# Atmega328p.net
KiCad netlist of a schematic drawn in Altium Designer
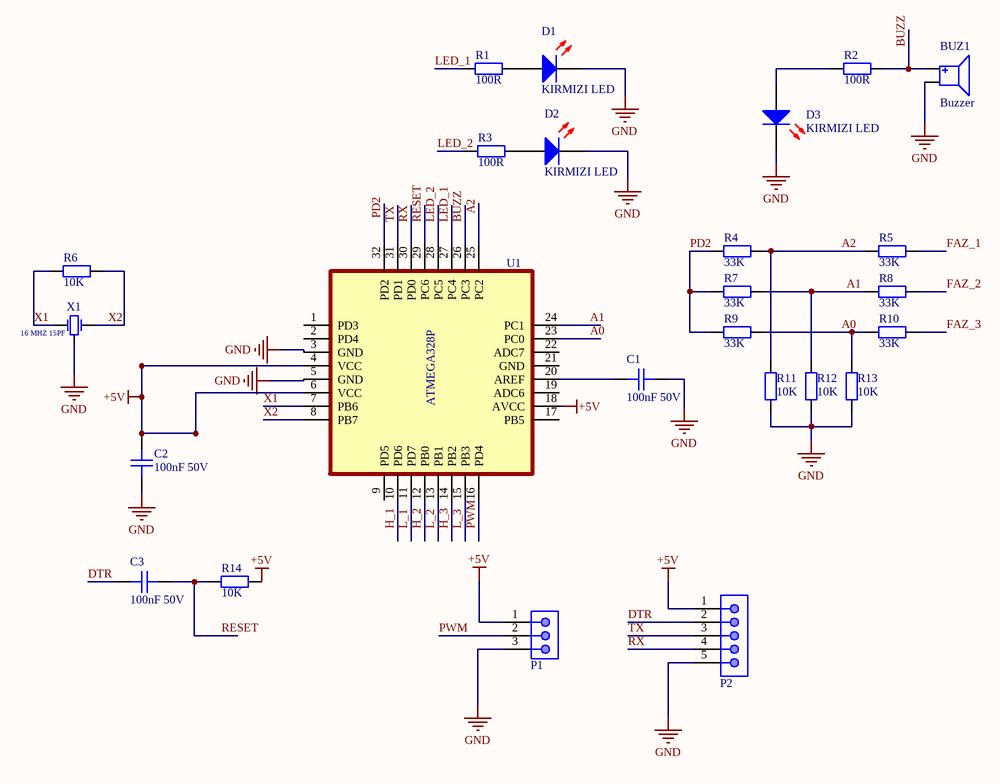
[diagram p0: Atmega328p.SchDoc]

(export (version "E")
  (design (tool "Eeschema 10.0.6"))
  (components
    (comp (ref "BUZ1")
      (value "BUZZER MAGN 3.6V 7.5X7.5MM SMD")
      (footprint "BUZ: CMT-7525")
      (fields (field (name "DEGER") "Buzzer"))
      (libsource (lib "PROJE") (part "Buzzer(CMT-7525-80-SMT-TR)"))
    )
    (comp (ref "C1")
      (value "CAP CER 0.1UF 50V X7R 0805")
      (footprint "CAP 0805/2012")
      (description "0.1µF ±10% 50V Ceramic Capacitor X7R 0805 (2012 Metric)")
      (fields (field (name "DEGER") "100nF 50V"))
      (libsource (lib "PROJE") (part "100nF 50V 0805"))
    )
    (comp (ref "C2")
      (value "CAP CER 0.1UF 50V X7R 0805")
      (footprint "CAP 0805/2012")
      (description "0.1µF ±10% 50V Ceramic Capacitor X7R 0805 (2012 Metric)")
      (fields (field (name "DEGER") "100nF 50V"))
      (libsource (lib "PROJE") (part "100nF 50V 0805"))
    )
    (comp (ref "C3")
      (value "CAP CER 0.1UF 50V X7R 0805")
      (footprint "CAP 0805/2012")
      (description "0.1µF ±10% 50V Ceramic Capacitor X7R 0805 (2012 Metric)")
      (fields (field (name "DEGER") "100nF 50V"))
      (libsource (lib "PROJE") (part "100nF 50V 0805"))
    )
    (comp (ref "D1")
      (value "Red 645nm LED Indication - Discrete 1.8V 0805")
      (footprint "SMD: LED 0805/2012 RED")
      (description "LED RED DIFFUSED 0805 SMD")
      (fields (field (name "DEGER") "KIRMIZI LED"))
      (libsource (lib "PROJE") (part "LED_Kırmızı"))
    )
    (comp (ref "D2")
      (value "Red 645nm LED Indication - Discrete 1.8V 0805")
      (footprint "SMD: LED 0805/2012 RED")
      (description "LED RED DIFFUSED 0805 SMD")
      (fields (field (name "DEGER") "KIRMIZI LED"))
      (libsource (lib "PROJE") (part "LED_Kırmızı"))
    )
    (comp (ref "D3")
      (value "Red 645nm LED Indication - Discrete 1.8V 0805")
      (footprint "SMD: LED 0805/2012 RED")
      (description "LED RED DIFFUSED 0805 SMD")
      (fields (field (name "DEGER") "KIRMIZI LED"))
      (libsource (lib "PROJE") (part "LED_Kırmızı"))
    )
    (comp (ref "P1")
      (value "WR-PHD 2.54 mm Angled Socket Header")
      (footprint "PWM_CONN")
      (libsource (lib "PROJE") (part "HDR(1X3)"))
    )
    (comp (ref "P2")
      (value "WR-PHD 2.54 mm Angled Socket Header")
      (footprint "TTL_CONN_5")
      (libsource (lib "PROJE") (part "HDR(1X5)"))
    )
    (comp (ref "R1")
      (value "RES SMD 100 OHM 1% 1/8W 0805")
      (footprint "RES_0805")
      (description "100 Ohms ±1% 0.125W, 1/8W Chip Resistor 0805 (2012 Metric) Moisture Resistant Thick Film")
      (fields (field (name "DEGER") "100R"))
      (libsource (lib "PROJE") (part "100R 0805"))
    )
    (comp (ref "R2")
      (value "RES SMD 100 OHM 1% 1/8W 0805")
      (footprint "RES_0805")
      (description "100 Ohms ±1% 0.125W, 1/8W Chip Resistor 0805 (2012 Metric) Moisture Resistant Thick Film")
      (fields (field (name "DEGER") "100R"))
      (libsource (lib "PROJE") (part "100R 0805"))
    )
    (comp (ref "R3")
      (value "RES SMD 100 OHM 1% 1/8W 0805")
      (footprint "RES_0805")
      (description "100 Ohms ±1% 0.125W, 1/8W Chip Resistor 0805 (2012 Metric) Moisture Resistant Thick Film")
      (fields (field (name "DEGER") "100R"))
      (libsource (lib "PROJE") (part "100R 0805"))
    )
    (comp (ref "R4")
      (value "RES SMD 33K OHM 1% 1/8W 0805")
      (footprint "RES_0805")
      (description "33 kOhms ±1% 0.125W, 1/8W Chip Resistor 0805 (2012 Metric) Moisture Resistant Thick Film")
      (fields (field (name "DEGER") "33K"))
      (libsource (lib "PROJE") (part "33K 0805"))
    )
    (comp (ref "R5")
      (value "RES SMD 33K OHM 1% 1/8W 0805")
      (footprint "RES_0805")
      (description "33 kOhms ±1% 0.125W, 1/8W Chip Resistor 0805 (2012 Metric) Moisture Resistant Thick Film")
      (fields (field (name "DEGER") "33K"))
      (libsource (lib "PROJE") (part "33K 0805"))
    )
    (comp (ref "R6")
      (value "RES SMD 10K OHM 1% 1/8W 0805")
      (footprint "RES_0805")
      (description "10 kOhms ±1% 0.125W, 1/8W Chip Resistor 0805 (2012 Metric) Moisture Resistant Thick Film")
      (fields (field (name "DEGER") "10K"))
      (libsource (lib "") (part "10K 0805_1"))
    )
    (comp (ref "R7")
      (value "RES SMD 33K OHM 1% 1/8W 0805")
      (footprint "RES_0805")
      (description "33 kOhms ±1% 0.125W, 1/8W Chip Resistor 0805 (2012 Metric) Moisture Resistant Thick Film")
      (fields (field (name "DEGER") "33K"))
      (libsource (lib "PROJE") (part "33K 0805"))
    )
    (comp (ref "R8")
      (value "RES SMD 33K OHM 1% 1/8W 0805")
      (footprint "RES_0805")
      (description "33 kOhms ±1% 0.125W, 1/8W Chip Resistor 0805 (2012 Metric) Moisture Resistant Thick Film")
      (fields (field (name "DEGER") "33K"))
      (libsource (lib "PROJE") (part "33K 0805"))
    )
    (comp (ref "R9")
      (value "RES SMD 33K OHM 1% 1/8W 0805")
      (footprint "RES_0805")
      (description "33 kOhms ±1% 0.125W, 1/8W Chip Resistor 0805 (2012 Metric) Moisture Resistant Thick Film")
      (fields (field (name "DEGER") "33K"))
      (libsource (lib "PROJE") (part "33K 0805"))
    )
    (comp (ref "R10")
      (value "RES SMD 33K OHM 1% 1/8W 0805")
      (footprint "RES_0805")
      (description "33 kOhms ±1% 0.125W, 1/8W Chip Resistor 0805 (2012 Metric) Moisture Resistant Thick Film")
      (fields (field (name "DEGER") "33K"))
      (libsource (lib "PROJE") (part "33K 0805"))
    )
    (comp (ref "R11")
      (value "RES SMD 10K OHM 1% 1/8W 0805")
      (footprint "RES_0805")
      (description "10 kOhms ±1% 0.125W, 1/8W Chip Resistor 0805 (2012 Metric) Moisture Resistant Thick Film")
      (fields (field (name "DEGER") "10K"))
      (libsource (lib "PROJE") (part "10K 0805"))
    )
    (comp (ref "R12")
      (value "RES SMD 10K OHM 1% 1/8W 0805")
      (footprint "RES_0805")
      (description "10 kOhms ±1% 0.125W, 1/8W Chip Resistor 0805 (2012 Metric) Moisture Resistant Thick Film")
      (fields (field (name "DEGER") "10K"))
      (libsource (lib "PROJE") (part "10K 0805"))
    )
    (comp (ref "R13")
      (value "RES SMD 10K OHM 1% 1/8W 0805")
      (footprint "RES_0805")
      (description "10 kOhms ±1% 0.125W, 1/8W Chip Resistor 0805 (2012 Metric) Moisture Resistant Thick Film")
      (fields (field (name "DEGER") "10K"))
      (libsource (lib "PROJE") (part "10K 0805"))
    )
    (comp (ref "R14")
      (value "RES SMD 10K OHM 1% 1/8W 0805")
      (footprint "RES_0805")
      (description "10 kOhms ±1% 0.125W, 1/8W Chip Resistor 0805 (2012 Metric) Moisture Resistant Thick Film")
      (fields (field (name "DEGER") "10K"))
      (libsource (lib "") (part "10K 0805_1"))
    )
    (comp (ref "U1")
      (value "IC MCU 8BIT 32KB FLASH 32TQFP")
      (footprint "TQFP32")
      (description "AVR AVR® ATmega Microcontroller IC 8-Bit 20MHz 32KB (16K x 16) FLASH 32-TQFP (7x7)")
      (fields (field (name "DEGER") "ATMEGA328P"))
      (libsource (lib "PROJE") (part "ATMEGA328P"))
    )
    (comp (ref "X1")
      (value "CERAMIC RES 16.0000MHZ 15PF SMD")
      (footprint "CRYSTAL_16MHZ(CTSE16)")
      (description "16MHz Ceramic Resonator Built in Capacitor 15pF ±0.3%  -20°C ~ 80°C Surface Mount")
      (fields (field (name "DEGER") "16 MHZ 15PF"))
      (libsource (lib "PROJE") (part "CRYSTAL 16.0000MHZ(CSTCE16M0V53-R0)"))
    )
  )
  (nets
    (net (code "1") (name "+5V") (class "Default")
      (node (ref "C2") (pin "2") (pinfunction "2_2") (pintype "passive"))
      (node (ref "P1") (pin "1") (pinfunction "1_1") (pintype "passive"))
      (node (ref "P2") (pin "1") (pinfunction "1_1") (pintype "passive"))
      (node (ref "R14") (pin "2") (pinfunction "2_2") (pintype "passive"))
      (node (ref "U1") (pin "18") (pinfunction "AVCC_18") (pintype "passive"))
      (node (ref "U1") (pin "4") (pinfunction "VCC_4") (pintype "passive"))
      (node (ref "U1") (pin "6") (pinfunction "VCC_6") (pintype "passive"))
    )
    (net (code "2") (name "/A0") (class "Default")
      (node (ref "R10") (pin "1") (pinfunction "1_1") (pintype "passive"))
      (node (ref "R13") (pin "2") (pinfunction "2_2") (pintype "passive"))
      (node (ref "R9") (pin "2") (pinfunction "2_2") (pintype "passive"))
      (node (ref "U1") (pin "23") (pinfunction "PC0_23") (pintype "passive"))
    )
    (net (code "3") (name "/A1") (class "Default")
      (node (ref "R12") (pin "2") (pinfunction "2_2") (pintype "passive"))
      (node (ref "R7") (pin "2") (pinfunction "2_2") (pintype "passive"))
      (node (ref "R8") (pin "1") (pinfunction "1_1") (pintype "passive"))
      (node (ref "U1") (pin "24") (pinfunction "PC1_24") (pintype "passive"))
    )
    (net (code "4") (name "/A2") (class "Default")
      (node (ref "R11") (pin "2") (pinfunction "2_2") (pintype "passive"))
      (node (ref "R4") (pin "2") (pinfunction "2_2") (pintype "passive"))
      (node (ref "R5") (pin "1") (pinfunction "1_1") (pintype "passive"))
      (node (ref "U1") (pin "25") (pinfunction "PC2_25") (pintype "passive"))
    )
    (net (code "5") (name "/BUZZ") (class "Default")
      (node (ref "BUZ1") (pin "1") (pinfunction "Positive_1") (pintype "passive"))
      (node (ref "R2") (pin "2") (pinfunction "2_2") (pintype "passive"))
      (node (ref "U1") (pin "26") (pinfunction "PC3_26") (pintype "passive"))
    )
    (net (code "6") (name "/DTR") (class "Default")
      (node (ref "C3") (pin "1") (pinfunction "1_1") (pintype "passive"))
      (node (ref "P2") (pin "2") (pinfunction "2_2") (pintype "passive"))
    )
    (net (code "7") (name "/FAZ_1") (class "Default")
      (node (ref "R5") (pin "2") (pinfunction "2_2") (pintype "passive"))
    )
    (net (code "8") (name "/FAZ_2") (class "Default")
      (node (ref "R8") (pin "2") (pinfunction "2_2") (pintype "passive"))
    )
    (net (code "9") (name "/FAZ_3") (class "Default")
      (node (ref "R10") (pin "2") (pinfunction "2_2") (pintype "passive"))
    )
    (net (code "10") (name "/H_1") (class "Default")
      (node (ref "U1") (pin "10") (pinfunction "PD6_10") (pintype "passive"))
    )
    (net (code "11") (name "/H_2") (class "Default")
      (node (ref "U1") (pin "12") (pinfunction "PB0_12") (pintype "passive"))
    )
    (net (code "12") (name "/H_3") (class "Default")
      (node (ref "U1") (pin "14") (pinfunction "PB2_14") (pintype "passive"))
    )
    (net (code "13") (name "/LED_1") (class "Default")
      (node (ref "R1") (pin "1") (pinfunction "1_1") (pintype "passive"))
      (node (ref "U1") (pin "27") (pinfunction "PC4_27") (pintype "passive"))
    )
    (net (code "14") (name "/LED_2") (class "Default")
      (node (ref "R3") (pin "1") (pinfunction "1_1") (pintype "passive"))
      (node (ref "U1") (pin "28") (pinfunction "PC5_28") (pintype "passive"))
    )
    (net (code "15") (name "/L_1") (class "Default")
      (node (ref "U1") (pin "11") (pinfunction "PD7_11") (pintype "passive"))
    )
    (net (code "16") (name "/L_2") (class "Default")
      (node (ref "U1") (pin "13") (pinfunction "PB1_13") (pintype "passive"))
    )
    (net (code "17") (name "/L_3") (class "Default")
      (node (ref "U1") (pin "15") (pinfunction "PB3_15") (pintype "passive"))
    )
    (net (code "18") (name "/PD2") (class "Default")
      (node (ref "R4") (pin "1") (pinfunction "1_1") (pintype "passive"))
      (node (ref "R7") (pin "1") (pinfunction "1_1") (pintype "passive"))
      (node (ref "R9") (pin "1") (pinfunction "1_1") (pintype "passive"))
      (node (ref "U1") (pin "32") (pinfunction "PD2_32") (pintype "passive"))
    )
    (net (code "19") (name "/PWM") (class "Default")
      (node (ref "P1") (pin "2") (pinfunction "2_2") (pintype "passive"))
      (node (ref "U1") (pin "16") (pinfunction "PD4_16") (pintype "passive"))
    )
    (net (code "20") (name "/RESET") (class "Default")
      (node (ref "C3") (pin "2") (pinfunction "2_2") (pintype "passive"))
      (node (ref "R14") (pin "1") (pinfunction "1_1") (pintype "passive"))
      (node (ref "U1") (pin "29") (pinfunction "PC6_29") (pintype "passive"))
    )
    (net (code "21") (name "/RX") (class "Default")
      (node (ref "P2") (pin "4") (pinfunction "4_4") (pintype "passive"))
      (node (ref "U1") (pin "30") (pinfunction "PD0_30") (pintype "passive"))
    )
    (net (code "22") (name "/TX") (class "Default")
      (node (ref "P2") (pin "3") (pinfunction "3_3") (pintype "passive"))
      (node (ref "U1") (pin "31") (pinfunction "PD1_31") (pintype "passive"))
    )
    (net (code "23") (name "/X1") (class "Default")
      (node (ref "R6") (pin "1") (pinfunction "1_1") (pintype "passive"))
      (node (ref "U1") (pin "7") (pinfunction "PB6_7") (pintype "passive"))
      (node (ref "X1") (pin "1") (pinfunction "OSC1_1") (pintype "passive"))
    )
    (net (code "24") (name "/X2") (class "Default")
      (node (ref "R6") (pin "2") (pinfunction "2_2") (pintype "passive"))
      (node (ref "U1") (pin "8") (pinfunction "PB7_8") (pintype "passive"))
      (node (ref "X1") (pin "3") (pinfunction "OSC2_3") (pintype "passive"))
    )
    (net (code "25") (name "GND") (class "Default")
      (node (ref "BUZ1") (pin "2") (pinfunction "Negative_2") (pintype "passive"))
      (node (ref "C1") (pin "1") (pinfunction "1_1") (pintype "passive"))
      (node (ref "C2") (pin "1") (pinfunction "1_1") (pintype "passive"))
      (node (ref "D1") (pin "2") (pinfunction "K_2") (pintype "passive"))
      (node (ref "D2") (pin "2") (pinfunction "K_2") (pintype "passive"))
      (node (ref "D3") (pin "2") (pinfunction "K_2") (pintype "passive"))
      (node (ref "P1") (pin "3") (pinfunction "3_3") (pintype "passive"))
      (node (ref "P2") (pin "5") (pinfunction "5_5") (pintype "passive"))
      (node (ref "R11") (pin "1") (pinfunction "1_1") (pintype "passive"))
      (node (ref "R12") (pin "1") (pinfunction "1_1") (pintype "passive"))
      (node (ref "R13") (pin "1") (pinfunction "1_1") (pintype "passive"))
      (node (ref "U1") (pin "3") (pinfunction "GND_3") (pintype "passive"))
      (node (ref "U1") (pin "5") (pinfunction "GND_5") (pintype "passive"))
      (node (ref "X1") (pin "2") (pinfunction "GND_2") (pintype "passive"))
    )
    (net (code "26") (name "Net-(D1-A)") (class "Default")
      (node (ref "D1") (pin "1") (pinfunction "A_1") (pintype "passive"))
      (node (ref "R1") (pin "2") (pinfunction "2_2") (pintype "passive"))
    )
    (net (code "27") (name "Net-(D2-A)") (class "Default")
      (node (ref "D2") (pin "1") (pinfunction "A_1") (pintype "passive"))
      (node (ref "R3") (pin "2") (pinfunction "2_2") (pintype "passive"))
    )
    (net (code "28") (name "Net-(D3-A)") (class "Default")
      (node (ref "D3") (pin "1") (pinfunction "A_1") (pintype "passive"))
      (node (ref "R2") (pin "1") (pinfunction "1_1") (pintype "passive"))
    )
    (net (code "29") (name "Net-(U1-AREF)") (class "Default")
      (node (ref "C1") (pin "2") (pinfunction "2_2") (pintype "passive"))
      (node (ref "U1") (pin "20") (pinfunction "AREF_20") (pintype "passive"))
    )
    (net (code "30") (name "unconnected-(U1-ADC6-Pad19)") (class "Default")
      (node (ref "U1") (pin "19") (pinfunction "ADC6_19") (pintype "passive"))
    )
    (net (code "31") (name "unconnected-(U1-ADC7-Pad22)") (class "Default")
      (node (ref "U1") (pin "22") (pinfunction "ADC7_22") (pintype "passive"))
    )
    (net (code "32") (name "unconnected-(U1-GND-Pad21)") (class "Default")
      (node (ref "U1") (pin "21") (pinfunction "GND_21") (pintype "passive"))
    )
    (net (code "33") (name "unconnected-(U1-PB5-Pad17)") (class "Default")
      (node (ref "U1") (pin "17") (pinfunction "PB5_17") (pintype "passive"))
    )
    (net (code "34") (name "unconnected-(U1-PD3-Pad1)") (class "Default")
      (node (ref "U1") (pin "1") (pinfunction "PD3_1") (pintype "passive"))
    )
    (net (code "35") (name "unconnected-(U1-PD4-Pad2)") (class "Default")
      (node (ref "U1") (pin "2") (pinfunction "PD4_2") (pintype "passive"))
    )
    (net (code "36") (name "unconnected-(U1-PD5-Pad9)") (class "Default")
      (node (ref "U1") (pin "9") (pinfunction "PD5_9") (pintype "passive"))
    )
  )
)
